# ThrowBot_TX_Main_Board.net
KiCad netlist of a schematic drawn in Altium Designer
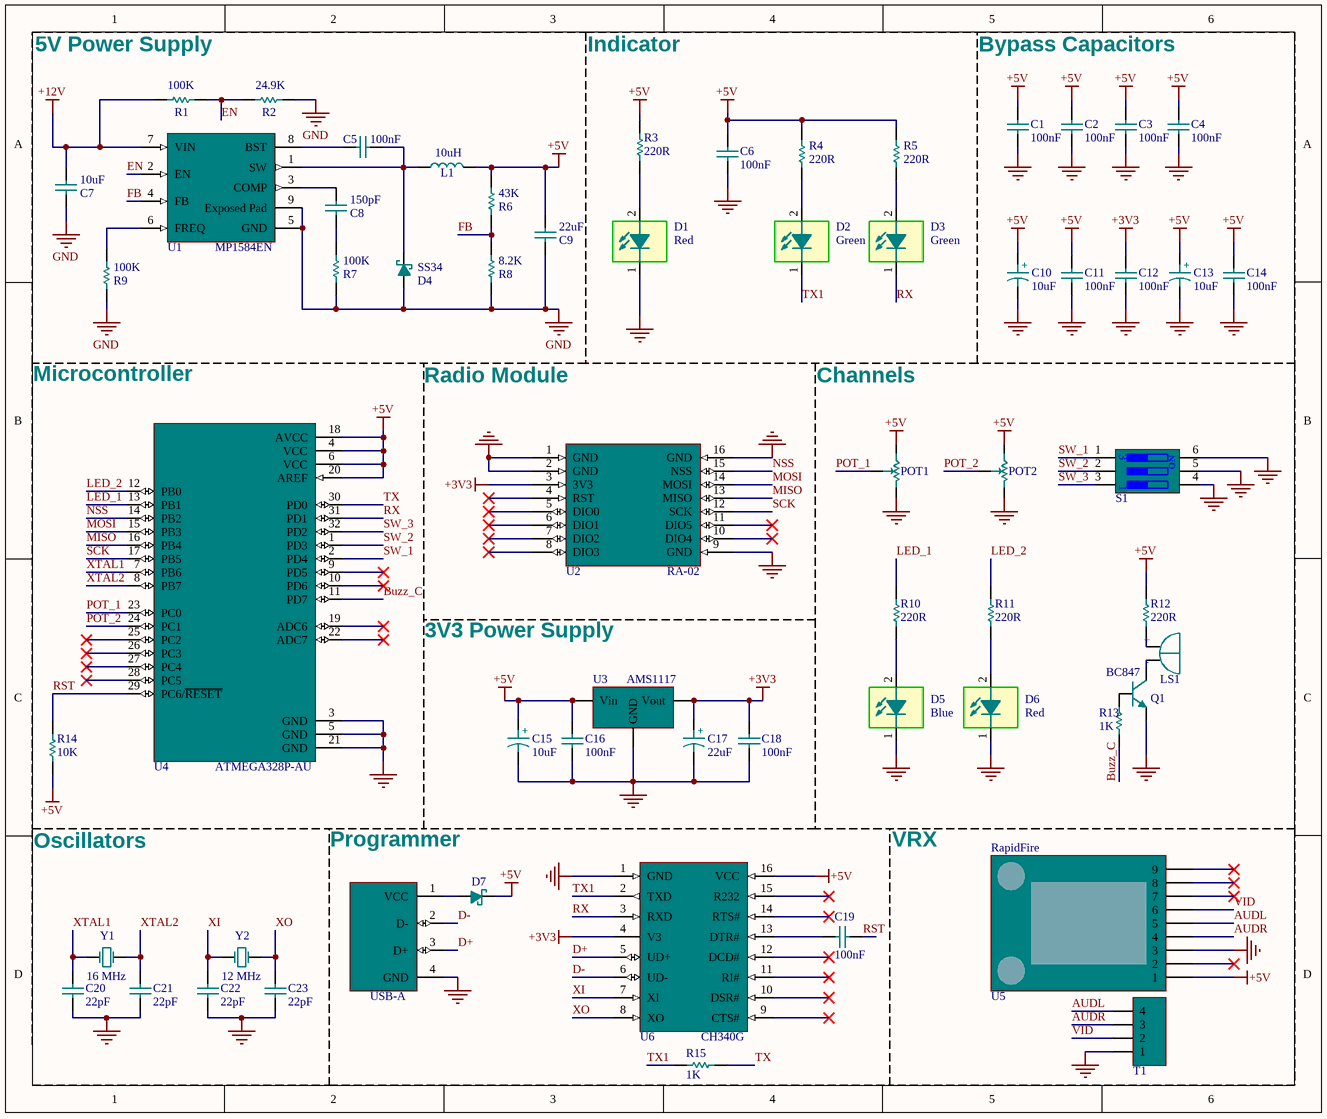
[diagram p0: ThrowBot_TX_Main_Board.SchDoc]

(export (version "E")
  (design (tool "Eeschema 10.0.6"))
  (components
    (comp (ref "C1")
      (value "Cap")
      (footprint "CAP 1206")
      (description "AVCC Cap")
      (fields (field (name "VAL-1") "100nF"))
      (libsource (lib "Throwbot") (part "Cap"))
    )
    (comp (ref "C2")
      (value "Cap")
      (footprint "CAP 1206")
      (description "VCC Cap")
      (fields (field (name "VAL-1") "100nF"))
      (libsource (lib "Throwbot") (part "Cap"))
    )
    (comp (ref "C3")
      (value "Cap")
      (footprint "CAP 1206")
      (description "VCC Cap")
      (fields (field (name "VAL-1") "100nF"))
      (libsource (lib "Throwbot") (part "Cap"))
    )
    (comp (ref "C4")
      (value "Cap")
      (footprint "CAP 1206")
      (description "AREF Cap")
      (fields (field (name "VAL-1") "100nF"))
      (libsource (lib "Throwbot") (part "Cap"))
    )
    (comp (ref "C5")
      (value "Cap")
      (footprint "CAP 1206")
      (description "1206 Capacitor")
      (fields (field (name "VAL-1") "100nF"))
      (libsource (lib "Throwbot") (part "Cap"))
    )
    (comp (ref "C6")
      (value "Cap")
      (footprint "CAP 1206")
      (description "USB to TTL Cap")
      (fields (field (name "VAL-1") "100nF"))
      (libsource (lib "Throwbot") (part "Cap"))
    )
    (comp (ref "C7")
      (value "Cap")
      (footprint "CAP 1206")
      (description "1206 Capacitor")
      (fields (field (name "VAL-4") "10uF"))
      (libsource (lib "Throwbot") (part "Cap"))
    )
    (comp (ref "C8")
      (value "Cap")
      (footprint "CAP 1206")
      (description "1206 Capacitor")
      (fields (field (name "VAL-5") "150pF"))
      (libsource (lib "Throwbot") (part "Cap"))
    )
    (comp (ref "C9")
      (value "Cap")
      (footprint "CAP 1206")
      (description "1206 Capacitor")
      (fields (field (name "VAL-3") "22uF"))
      (libsource (lib "Throwbot") (part "Cap"))
    )
    (comp (ref "C10")
      (value "Cap BiPolar")
      (footprint "CAP Tantalum Size B")
      (description "USB to TTL Cap")
      (fields (field (name "VAL-1") "10uF"))
      (libsource (lib "Throwbot") (part "Cap BiPolar"))
    )
    (comp (ref "C11")
      (value "Cap")
      (footprint "CAP 1206")
      (description "USB to TTL Cap")
      (fields (field (name "VAL-1") "100nF"))
      (libsource (lib "Throwbot") (part "Cap"))
    )
    (comp (ref "C12")
      (value "Cap")
      (footprint "CAP 1206")
      (description "USB to TTL Cap")
      (fields (field (name "VAL-1") "100nF"))
      (libsource (lib "Throwbot") (part "Cap"))
    )
    (comp (ref "C13")
      (value "Cap BiPolar")
      (footprint "CAP Tantalum Size B")
      (description "RapidFire Cap")
      (fields (field (name "VAL-1") "10uF"))
      (libsource (lib "Throwbot") (part "Cap BiPolar"))
    )
    (comp (ref "C14")
      (value "Cap")
      (footprint "CAP 1206")
      (description "RapidFire Cap")
      (fields (field (name "VAL-1") "100nF"))
      (libsource (lib "Throwbot") (part "Cap"))
    )
    (comp (ref "C15")
      (value "Cap BiPolar")
      (footprint "CAP Tantalum Size B")
      (description "3.3V Regulator Cap")
      (fields (field (name "VAL-1") "10uF"))
      (libsource (lib "Throwbot") (part "Cap BiPolar"))
    )
    (comp (ref "C16")
      (value "Cap")
      (footprint "CAP 1206")
      (description "3.3V Regulator Cap")
      (fields (field (name "VAL-1") "100nF"))
      (libsource (lib "Throwbot") (part "Cap"))
    )
    (comp (ref "C17")
      (value "Cap BiPolar")
      (footprint "CAP Tantalum Size B")
      (description "3.3V Regulator Cap")
      (fields (field (name "VAL-1") "22uF"))
      (libsource (lib "Throwbot") (part "Cap BiPolar"))
    )
    (comp (ref "C18")
      (value "Cap")
      (footprint "CAP 1206")
      (description "3.3V Regulator Cap")
      (fields (field (name "VAL-1") "100nF"))
      (libsource (lib "Throwbot") (part "Cap"))
    )
    (comp (ref "C19")
      (value "Cap")
      (footprint "CAP 1206")
      (description "Programmer Cap")
      (fields (field (name "VAL-1") "100nF"))
      (libsource (lib "Throwbot") (part "Cap"))
    )
    (comp (ref "C20")
      (value "Cap")
      (footprint "CAP 1206")
      (description "1206 Capacitor")
      (fields (field (name "VAL-2") "22pF"))
      (libsource (lib "Throwbot") (part "Cap"))
    )
    (comp (ref "C21")
      (value "Cap")
      (footprint "CAP 1206")
      (description "1206 Capacitor")
      (fields (field (name "VAL-2") "22pF"))
      (libsource (lib "Throwbot") (part "Cap"))
    )
    (comp (ref "C22")
      (value "Cap")
      (footprint "CAP 1206")
      (description "1206 Capacitor")
      (fields (field (name "VAL-2") "22pF"))
      (libsource (lib "Throwbot") (part "Cap"))
    )
    (comp (ref "C23")
      (value "Cap")
      (footprint "CAP 1206")
      (description "1206 Capacitor")
      (fields (field (name "VAL-2") "22pF"))
      (libsource (lib "Throwbot") (part "Cap"))
    )
    (comp (ref "D1")
      (value "LED")
      (footprint "LED 1206")
      (fields (field (name "COLOR-2") "Red"))
      (libsource (lib "Throwbot") (part "LED"))
    )
    (comp (ref "D2")
      (value "LED")
      (footprint "LED 1206")
      (fields (field (name "COLOR-3") "Green"))
      (libsource (lib "Throwbot") (part "LED"))
    )
    (comp (ref "D3")
      (value "LED")
      (footprint "LED 1206")
      (fields (field (name "COLOR-3") "Green"))
      (libsource (lib "Throwbot") (part "LED"))
    )
    (comp (ref "D4")
      (value "SS34")
      (footprint "SS34")
      (description "Diode Schottky 40 V 3A Surface Mount SMA")
      (fields (field (name "MF") "MDD"))
      (libsource (lib "Throwbot") (part "SS34"))
    )
    (comp (ref "D5")
      (value "LED")
      (footprint "LED 1206")
      (fields (field (name "COLOR-1") "Blue"))
      (libsource (lib "Throwbot") (part "LED"))
    )
    (comp (ref "D6")
      (value "LED")
      (footprint "LED 1206")
      (fields (field (name "COLOR-2") "Red"))
      (libsource (lib "Throwbot") (part "LED"))
    )
    (comp (ref "D7")
      (value "SS34")
      (footprint "SS34")
      (description "Diode Schottky 40 V 3A Surface Mount SMA")
      (libsource (lib "Throwbot") (part "SS34"))
    )
    (comp (ref "L1")
      (value "10uH")
      (footprint "IND 10uH")
      (description "Inductor")
      (fields (field (name "PUBLISHER") "Altium Limited"))
      (libsource (lib "Throwbot") (part "Inductor"))
    )
    (comp (ref "LS1")
      (value "Buzzer-5V")
      (footprint "Buzzer-5V")
      (libsource (lib "Throwbot") (part "Buzzer-5V"))
    )
    (comp (ref "POT1") (value "Pot") (footprint "Pot") (libsource (lib "Throwbot") (part "Pot")))
    (comp (ref "POT2") (value "Pot") (footprint "Pot") (libsource (lib "Throwbot") (part "Pot")))
    (comp (ref "Q1")
      (value "BC847")
      (footprint "BC847-SOT23")
      (description "NPN General-purpose Transistor")
      (fields (field (name "DESIGNER") "Abbas Basereh"))
      (libsource (lib "Throwbot") (part "BC847"))
    )
    (comp (ref "R1")
      (value "Resistor")
      (footprint "RES 1206")
      (fields (field (name "VAL-4") "100K"))
      (libsource (lib "Throwbot") (part "Resistor"))
    )
    (comp (ref "R2")
      (value "Resistor")
      (footprint "RES 1206")
      (fields (field (name "VAL-5") "24.9K"))
      (libsource (lib "Throwbot") (part "Resistor"))
    )
    (comp (ref "R3")
      (value "Resistor")
      (footprint "RES 1206")
      (fields (field (name "VAL-3") "220R"))
      (libsource (lib "Throwbot") (part "Resistor"))
    )
    (comp (ref "R4")
      (value "Resistor")
      (footprint "RES 1206")
      (fields (field (name "VAL-3") "220R"))
      (libsource (lib "Throwbot") (part "Resistor"))
    )
    (comp (ref "R5")
      (value "Resistor")
      (footprint "RES 1206")
      (fields (field (name "VAL-3") "220R"))
      (libsource (lib "Throwbot") (part "Resistor"))
    )
    (comp (ref "R6")
      (value "Resistor")
      (footprint "RES 1206")
      (fields (field (name "VAL-7") "43K"))
      (libsource (lib "Throwbot") (part "Resistor"))
    )
    (comp (ref "R7")
      (value "Resistor")
      (footprint "RES 1206")
      (fields (field (name "VAL-4") "100K"))
      (libsource (lib "Throwbot") (part "Resistor"))
    )
    (comp (ref "R8")
      (value "Resistor")
      (footprint "RES 1206")
      (fields (field (name "VAL-6") "8.2K"))
      (libsource (lib "Throwbot") (part "Resistor"))
    )
    (comp (ref "R9")
      (value "Resistor")
      (footprint "RES 1206")
      (fields (field (name "VAL-4") "100K"))
      (libsource (lib "Throwbot") (part "Resistor"))
    )
    (comp (ref "R10")
      (value "Resistor")
      (footprint "RES 1206")
      (fields (field (name "VAL-3") "220R"))
      (libsource (lib "Throwbot") (part "Resistor"))
    )
    (comp (ref "R11")
      (value "Resistor")
      (footprint "RES 1206")
      (fields (field (name "VAL-3") "220R"))
      (libsource (lib "Throwbot") (part "Resistor"))
    )
    (comp (ref "R12")
      (value "Resistor")
      (footprint "RES 1206")
      (fields (field (name "VAL-3") "220R"))
      (libsource (lib "Throwbot") (part "Resistor"))
    )
    (comp (ref "R13")
      (value "Resistor")
      (footprint "RES 1206")
      (fields (field (name "VAL-1") "1K"))
      (libsource (lib "Throwbot") (part "Resistor"))
    )
    (comp (ref "R14")
      (value "Resistor")
      (footprint "RES 1206")
      (fields (field (name "VAL-2") "10K"))
      (libsource (lib "Throwbot") (part "Resistor"))
    )
    (comp (ref "R15")
      (value "Resistor")
      (footprint "RES 1206")
      (fields (field (name "VAL-1") "1K"))
      (libsource (lib "Throwbot") (part "Resistor"))
    )
    (comp (ref "S1")
      (value "DIP Switch x3")
      (footprint "DIP Switch x3")
      (libsource (lib "Throwbot") (part "DIP Switch x3"))
    )
    (comp (ref "T1")
      (value "4 Pin Socket")
      (footprint "XH-4AW")
      (libsource (lib "Throwbot") (part "4 Pin Socket"))
    )
    (comp (ref "U1")
      (value "MP1584EN")
      (footprint "MP1584EN")
      (fields (field (name "MF") "Monolithic Power"))
      (libsource (lib "Throwbot") (part "MP1584EN"))
    )
    (comp (ref "U2")
      (value "RA-02")
      (footprint "RA-02")
      (description "LoRa RA-02")
      (libsource (lib "Throwbot") (part "RA-02"))
    )
    (comp (ref "U3")
      (value "AMS1117")
      (footprint "AMS1117")
      (description "3V3 Regulator")
      (libsource (lib "Throwbot") (part "AMS1117"))
    )
    (comp (ref "U4")
      (value "ATMEGA328P-AU")
      (footprint "ATmega328")
      (description "ATmega 328 Microcontroller")
      (libsource (lib "Throwbot") (part "ATMEGA328P-AU"))
    )
    (comp (ref "U5")
      (value "RapidFire")
      (footprint "RapidFire")
      (libsource (lib "Throwbot") (part "RapidFire"))
    )
    (comp (ref "U6") (value "CH340G") (footprint "CH340G") (libsource (lib "Throwbot") (part "CH340G")))
    (comp (ref "USB1") (value "USB-A") (footprint "USB-A-SMD") (libsource (lib "Throwbot") (part "USB-A")))
    (comp (ref "Y1")
      (value "XTAL")
      (footprint "Crystal-5032")
      (description "XTAL Crystal")
      (fields (field (name "VAL-2") "16 MHz"))
      (libsource (lib "Throwbot") (part "XTAL"))
    )
    (comp (ref "Y2")
      (value "XTAL")
      (footprint "Crystal-5032")
      (description "XTAL Crystal")
      (fields (field (name "VAL-1") "12 MHz"))
      (libsource (lib "Throwbot") (part "XTAL"))
    )
  )
  (nets
    (net (code "1") (name "+3V3") (class "Default")
      (node (ref "C12") (pin "1") (pinfunction "1_1") (pintype "passive"))
      (node (ref "C17") (pin "1") (pinfunction "1_1") (pintype "passive"))
      (node (ref "C18") (pin "1") (pinfunction "1_1") (pintype "passive"))
      (node (ref "U2") (pin "3") (pinfunction "3V3_3") (pintype "input"))
      (node (ref "U3") (pin "2") (pinfunction "Vout_2") (pintype "power_in"))
      (node (ref "U6") (pin "4") (pinfunction "V3_4") (pintype "passive"))
    )
    (net (code "2") (name "+5V") (class "Default")
      (node (ref "C1") (pin "1") (pinfunction "1_1") (pintype "passive"))
      (node (ref "C10") (pin "1") (pinfunction "1_1") (pintype "passive"))
      (node (ref "C11") (pin "1") (pinfunction "1_1") (pintype "passive"))
      (node (ref "C13") (pin "1") (pinfunction "1_1") (pintype "passive"))
      (node (ref "C14") (pin "1") (pinfunction "1_1") (pintype "passive"))
      (node (ref "C15") (pin "1") (pinfunction "1_1") (pintype "passive"))
      (node (ref "C16") (pin "1") (pinfunction "1_1") (pintype "passive"))
      (node (ref "C2") (pin "1") (pinfunction "1_1") (pintype "passive"))
      (node (ref "C3") (pin "1") (pinfunction "1_1") (pintype "passive"))
      (node (ref "C4") (pin "1") (pinfunction "1_1") (pintype "passive"))
      (node (ref "C6") (pin "1") (pinfunction "1_1") (pintype "passive"))
      (node (ref "C9") (pin "2") (pinfunction "2_2") (pintype "passive"))
      (node (ref "D7") (pin "2") (pinfunction "K_2") (pintype "passive"))
      (node (ref "L1") (pin "2") (pinfunction "2_2") (pintype "passive"))
      (node (ref "POT1") (pin "1") (pinfunction "CCW_1") (pintype "passive"))
      (node (ref "POT2") (pin "1") (pinfunction "CCW_1") (pintype "passive"))
      (node (ref "R12") (pin "2") (pinfunction "2_2") (pintype "passive"))
      (node (ref "R14") (pin "2") (pinfunction "2_2") (pintype "passive"))
      (node (ref "R3") (pin "2") (pinfunction "2_2") (pintype "passive"))
      (node (ref "R4") (pin "1") (pinfunction "1_1") (pintype "passive"))
      (node (ref "R5") (pin "1") (pinfunction "1_1") (pintype "passive"))
      (node (ref "R6") (pin "2") (pinfunction "2_2") (pintype "passive"))
      (node (ref "U3") (pin "3") (pinfunction "Vin_3") (pintype "power_in"))
      (node (ref "U4") (pin "18") (pinfunction "AVCC_18") (pintype "power_in"))
      (node (ref "U4") (pin "20") (pinfunction "AREF_20") (pintype "input"))
      (node (ref "U4") (pin "4") (pinfunction "VCC_4") (pintype "power_in"))
      (node (ref "U4") (pin "6") (pinfunction "VCC_6") (pintype "power_in"))
      (node (ref "U5") (pin "1") (pinfunction "1_1") (pintype "passive"))
      (node (ref "U6") (pin "16") (pinfunction "VCC_16") (pintype "input"))
    )
    (net (code "3") (name "+12V") (class "Default")
      (node (ref "C7") (pin "2") (pinfunction "2_2") (pintype "passive"))
      (node (ref "R1") (pin "2") (pinfunction "2_2") (pintype "passive"))
      (node (ref "U1") (pin "7") (pinfunction "VIN_7") (pintype "input"))
    )
    (net (code "4") (name "/AUDL") (class "Default")
      (node (ref "T1") (pin "4") (pinfunction "4_4") (pintype "passive"))
      (node (ref "U5") (pin "5") (pinfunction "5_5") (pintype "passive"))
    )
    (net (code "5") (name "/AUDR") (class "Default")
      (node (ref "T1") (pin "3") (pinfunction "3_3") (pintype "passive"))
      (node (ref "U5") (pin "4") (pinfunction "4_4") (pintype "passive"))
    )
    (net (code "6") (name "/Buzz_C") (class "Default")
      (node (ref "R13") (pin "1") (pinfunction "1_1") (pintype "passive"))
      (node (ref "U4") (pin "11") (pinfunction "PD7_11") (pintype "bidirectional"))
    )
    (net (code "7") (name "/D+") (class "Default")
      (node (ref "U6") (pin "5") (pinfunction "UD+_5") (pintype "bidirectional"))
      (node (ref "USB1") (pin "3") (pinfunction "D+_3") (pintype "bidirectional"))
    )
    (net (code "8") (name "/D-") (class "Default")
      (node (ref "U6") (pin "6") (pinfunction "UD-_6") (pintype "bidirectional"))
      (node (ref "USB1") (pin "2") (pinfunction "D-_2") (pintype "bidirectional"))
    )
    (net (code "9") (name "/EN") (class "Default")
      (node (ref "R1") (pin "1") (pinfunction "1_1") (pintype "passive"))
      (node (ref "R2") (pin "1") (pinfunction "1_1") (pintype "passive"))
      (node (ref "U1") (pin "2") (pinfunction "EN_2") (pintype "input"))
    )
    (net (code "10") (name "/FB") (class "Default")
      (node (ref "R6") (pin "1") (pinfunction "1_1") (pintype "passive"))
      (node (ref "R8") (pin "2") (pinfunction "2_2") (pintype "passive"))
      (node (ref "U1") (pin "4") (pinfunction "FB_4") (pintype "input"))
    )
    (net (code "11") (name "/LED_1") (class "Default")
      (node (ref "R10") (pin "2") (pinfunction "2_2") (pintype "passive"))
      (node (ref "U4") (pin "13") (pinfunction "PB1_13") (pintype "bidirectional"))
    )
    (net (code "12") (name "/LED_2") (class "Default")
      (node (ref "R11") (pin "2") (pinfunction "2_2") (pintype "passive"))
      (node (ref "U4") (pin "12") (pinfunction "PB0_12") (pintype "bidirectional"))
    )
    (net (code "13") (name "/MISO") (class "Default")
      (node (ref "U2") (pin "13") (pinfunction "MISO_13") (pintype "bidirectional"))
      (node (ref "U4") (pin "16") (pinfunction "PB4_16") (pintype "bidirectional"))
    )
    (net (code "14") (name "/MOSI") (class "Default")
      (node (ref "U2") (pin "14") (pinfunction "MOSI_14") (pintype "bidirectional"))
      (node (ref "U4") (pin "15") (pinfunction "PB3_15") (pintype "bidirectional"))
    )
    (net (code "15") (name "/NSS") (class "Default")
      (node (ref "U2") (pin "15") (pinfunction "NSS_15") (pintype "bidirectional"))
      (node (ref "U4") (pin "14") (pinfunction "PB2_14") (pintype "bidirectional"))
    )
    (net (code "16") (name "/POT_1") (class "Default")
      (node (ref "POT1") (pin "3") (pinfunction "SetPoint_3") (pintype "passive"))
      (node (ref "U4") (pin "23") (pinfunction "PC0_23") (pintype "bidirectional"))
    )
    (net (code "17") (name "/POT_2") (class "Default")
      (node (ref "POT2") (pin "3") (pinfunction "SetPoint_3") (pintype "passive"))
      (node (ref "U4") (pin "24") (pinfunction "PC1_24") (pintype "bidirectional"))
    )
    (net (code "18") (name "/RST") (class "Default")
      (node (ref "C19") (pin "1") (pinfunction "1_1") (pintype "passive"))
      (node (ref "R14") (pin "1") (pinfunction "1_1") (pintype "passive"))
      (node (ref "U4") (pin "29") (pinfunction "PC6/~{RESET}_29") (pintype "bidirectional"))
    )
    (net (code "19") (name "/RX") (class "Default")
      (node (ref "D3") (pin "1") (pinfunction "1_1") (pintype "passive"))
      (node (ref "U4") (pin "31") (pinfunction "PD1_31") (pintype "bidirectional"))
      (node (ref "U6") (pin "3") (pinfunction "RXD_3") (pintype "input"))
    )
    (net (code "20") (name "/SCK") (class "Default")
      (node (ref "U2") (pin "12") (pinfunction "SCK_12") (pintype "bidirectional"))
      (node (ref "U4") (pin "17") (pinfunction "PB5_17") (pintype "bidirectional"))
    )
    (net (code "21") (name "/SW_1") (class "Default")
      (node (ref "S1") (pin "1") (pinfunction "1_1") (pintype "passive"))
      (node (ref "U4") (pin "2") (pinfunction "PD4_2") (pintype "bidirectional"))
    )
    (net (code "22") (name "/SW_2") (class "Default")
      (node (ref "S1") (pin "2") (pinfunction "2_2") (pintype "passive"))
      (node (ref "U4") (pin "1") (pinfunction "PD3_1") (pintype "bidirectional"))
    )
    (net (code "23") (name "/SW_3") (class "Default")
      (node (ref "S1") (pin "3") (pinfunction "3_3") (pintype "passive"))
      (node (ref "U4") (pin "32") (pinfunction "PD2_32") (pintype "bidirectional"))
    )
    (net (code "24") (name "/TX") (class "Default")
      (node (ref "R15") (pin "2") (pinfunction "2_2") (pintype "passive"))
      (node (ref "U4") (pin "30") (pinfunction "PD0_30") (pintype "bidirectional"))
    )
    (net (code "25") (name "/TX1") (class "Default")
      (node (ref "D2") (pin "1") (pinfunction "1_1") (pintype "passive"))
      (node (ref "R15") (pin "1") (pinfunction "1_1") (pintype "passive"))
      (node (ref "U6") (pin "2") (pinfunction "TXD_2") (pintype "output"))
    )
    (net (code "26") (name "/VID") (class "Default")
      (node (ref "T1") (pin "2") (pinfunction "2_2") (pintype "passive"))
      (node (ref "U5") (pin "6") (pinfunction "6_6") (pintype "passive"))
    )
    (net (code "27") (name "/XI") (class "Default")
      (node (ref "C22") (pin "2") (pinfunction "2_2") (pintype "passive"))
      (node (ref "U6") (pin "7") (pinfunction "XI_7") (pintype "input"))
      (node (ref "Y2") (pin "1") (pinfunction "OSC1_1") (pintype "passive"))
    )
    (net (code "28") (name "/XO") (class "Default")
      (node (ref "C23") (pin "2") (pinfunction "2_2") (pintype "passive"))
      (node (ref "U6") (pin "8") (pinfunction "XO_8") (pintype "input"))
      (node (ref "Y2") (pin "2") (pinfunction "OSC2_2") (pintype "passive"))
    )
    (net (code "29") (name "/XTAL1") (class "Default")
      (node (ref "C20") (pin "2") (pinfunction "2_2") (pintype "passive"))
      (node (ref "U4") (pin "7") (pinfunction "PB6_7") (pintype "bidirectional"))
      (node (ref "Y1") (pin "1") (pinfunction "OSC1_1") (pintype "passive"))
    )
    (net (code "30") (name "/XTAL2") (class "Default")
      (node (ref "C21") (pin "2") (pinfunction "2_2") (pintype "passive"))
      (node (ref "U4") (pin "8") (pinfunction "PB7_8") (pintype "bidirectional"))
      (node (ref "Y1") (pin "2") (pinfunction "OSC2_2") (pintype "passive"))
    )
    (net (code "31") (name "GND") (class "Default")
      (node (ref "C1") (pin "2") (pinfunction "2_2") (pintype "passive"))
      (node (ref "C10") (pin "2") (pinfunction "2_2") (pintype "passive"))
      (node (ref "C11") (pin "2") (pinfunction "2_2") (pintype "passive"))
      (node (ref "C12") (pin "2") (pinfunction "2_2") (pintype "passive"))
      (node (ref "C13") (pin "2") (pinfunction "2_2") (pintype "passive"))
      (node (ref "C14") (pin "2") (pinfunction "2_2") (pintype "passive"))
      (node (ref "C15") (pin "2") (pinfunction "2_2") (pintype "passive"))
      (node (ref "C16") (pin "2") (pinfunction "2_2") (pintype "passive"))
      (node (ref "C17") (pin "2") (pinfunction "2_2") (pintype "passive"))
      (node (ref "C18") (pin "2") (pinfunction "2_2") (pintype "passive"))
      (node (ref "C2") (pin "2") (pinfunction "2_2") (pintype "passive"))
      (node (ref "C20") (pin "1") (pinfunction "1_1") (pintype "passive"))
      (node (ref "C21") (pin "1") (pinfunction "1_1") (pintype "passive"))
      (node (ref "C22") (pin "1") (pinfunction "1_1") (pintype "passive"))
      (node (ref "C23") (pin "1") (pinfunction "1_1") (pintype "passive"))
      (node (ref "C3") (pin "2") (pinfunction "2_2") (pintype "passive"))
      (node (ref "C4") (pin "2") (pinfunction "2_2") (pintype "passive"))
      (node (ref "C6") (pin "2") (pinfunction "2_2") (pintype "passive"))
      (node (ref "C7") (pin "1") (pinfunction "1_1") (pintype "passive"))
      (node (ref "C9") (pin "1") (pinfunction "1_1") (pintype "passive"))
      (node (ref "D1") (pin "1") (pinfunction "1_1") (pintype "passive"))
      (node (ref "D4") (pin "1") (pinfunction "A_1") (pintype "passive"))
      (node (ref "D5") (pin "1") (pinfunction "1_1") (pintype "passive"))
      (node (ref "D6") (pin "1") (pinfunction "1_1") (pintype "passive"))
      (node (ref "POT1") (pin "2") (pinfunction "CW_2") (pintype "passive"))
      (node (ref "POT2") (pin "2") (pinfunction "CW_2") (pintype "passive"))
      (node (ref "Q1") (pin "2") (pinfunction "E_2") (pintype "passive"))
      (node (ref "R2") (pin "2") (pinfunction "2_2") (pintype "passive"))
      (node (ref "R7") (pin "1") (pinfunction "1_1") (pintype "passive"))
      (node (ref "R8") (pin "1") (pinfunction "1_1") (pintype "passive"))
      (node (ref "R9") (pin "1") (pinfunction "1_1") (pintype "passive"))
      (node (ref "S1") (pin "4") (pinfunction "4_4") (pintype "passive"))
      (node (ref "S1") (pin "5") (pinfunction "5_5") (pintype "passive"))
      (node (ref "S1") (pin "6") (pinfunction "6_6") (pintype "passive"))
      (node (ref "T1") (pin "1") (pinfunction "1_1") (pintype "passive"))
      (node (ref "U1") (pin "5") (pinfunction "GND_5") (pintype "power_in"))
      (node (ref "U1") (pin "9") (pinfunction "Exposed_Pad_9") (pintype "power_in"))
      (node (ref "U2") (pin "1") (pinfunction "GND_1") (pintype "input"))
      (node (ref "U2") (pin "16") (pinfunction "GND_16") (pintype "input"))
      (node (ref "U2") (pin "2") (pinfunction "GND_2") (pintype "input"))
      (node (ref "U2") (pin "9") (pinfunction "GND_9") (pintype "input"))
      (node (ref "U3") (pin "1") (pinfunction "GND_1") (pintype "power_in"))
      (node (ref "U4") (pin "21") (pinfunction "GND_21") (pintype "power_in"))
      (node (ref "U4") (pin "3") (pinfunction "GND_3") (pintype "power_in"))
      (node (ref "U4") (pin "5") (pinfunction "GND_5") (pintype "power_in"))
      (node (ref "U5") (pin "3") (pinfunction "3_3") (pintype "passive"))
      (node (ref "U6") (pin "1") (pinfunction "GND_1") (pintype "input"))
      (node (ref "USB1") (pin "4") (pinfunction "GND_4") (pintype "power_in"))
    )
    (net (code "32") (name "Net-(C8-Pad1)") (class "Default")
      (node (ref "C8") (pin "1") (pinfunction "1_1") (pintype "passive"))
      (node (ref "R7") (pin "2") (pinfunction "2_2") (pintype "passive"))
    )
    (net (code "33") (name "Net-(D1-Pad2)") (class "Default")
      (node (ref "D1") (pin "2") (pinfunction "2_2") (pintype "passive"))
      (node (ref "R3") (pin "1") (pinfunction "1_1") (pintype "passive"))
    )
    (net (code "34") (name "Net-(D2-Pad2)") (class "Default")
      (node (ref "D2") (pin "2") (pinfunction "2_2") (pintype "passive"))
      (node (ref "R4") (pin "2") (pinfunction "2_2") (pintype "passive"))
    )
    (net (code "35") (name "Net-(D3-Pad2)") (class "Default")
      (node (ref "D3") (pin "2") (pinfunction "2_2") (pintype "passive"))
      (node (ref "R5") (pin "2") (pinfunction "2_2") (pintype "passive"))
    )
    (net (code "36") (name "Net-(D4-K)") (class "Default")
      (node (ref "C5") (pin "1") (pinfunction "1_1") (pintype "passive"))
      (node (ref "D4") (pin "2") (pinfunction "K_2") (pintype "passive"))
      (node (ref "L1") (pin "1") (pinfunction "1_1") (pintype "passive"))
      (node (ref "U1") (pin "1") (pinfunction "SW_1") (pintype "output"))
    )
    (net (code "37") (name "Net-(D5-Pad2)") (class "Default")
      (node (ref "D5") (pin "2") (pinfunction "2_2") (pintype "passive"))
      (node (ref "R10") (pin "1") (pinfunction "1_1") (pintype "passive"))
    )
    (net (code "38") (name "Net-(D6-Pad2)") (class "Default")
      (node (ref "D6") (pin "2") (pinfunction "2_2") (pintype "passive"))
      (node (ref "R11") (pin "1") (pinfunction "1_1") (pintype "passive"))
    )
    (net (code "39") (name "Net-(D7-A)") (class "Default")
      (node (ref "D7") (pin "1") (pinfunction "A_1") (pintype "passive"))
      (node (ref "USB1") (pin "1") (pinfunction "VCC_1") (pintype "power_in"))
    )
    (net (code "40") (name "Net-(LS1-NEG)") (class "Default")
      (node (ref "LS1") (pin "N") (pinfunction "NEG_N") (pintype "passive"))
      (node (ref "Q1") (pin "3") (pinfunction "C_3") (pintype "passive"))
    )
    (net (code "41") (name "Net-(LS1-POS)") (class "Default")
      (node (ref "LS1") (pin "P") (pinfunction "POS_P") (pintype "passive"))
      (node (ref "R12") (pin "1") (pinfunction "1_1") (pintype "passive"))
    )
    (net (code "42") (name "Net-(Q1-B)") (class "Default")
      (node (ref "Q1") (pin "1") (pinfunction "B_1") (pintype "passive"))
      (node (ref "R13") (pin "2") (pinfunction "2_2") (pintype "passive"))
    )
    (net (code "43") (name "Net-(U1-BST)") (class "Default")
      (node (ref "C5") (pin "2") (pinfunction "2_2") (pintype "passive"))
      (node (ref "U1") (pin "8") (pinfunction "BST_8") (pintype "passive"))
    )
    (net (code "44") (name "Net-(U1-COMP)") (class "Default")
      (node (ref "C8") (pin "2") (pinfunction "2_2") (pintype "passive"))
      (node (ref "U1") (pin "3") (pinfunction "COMP_3") (pintype "output"))
    )
    (net (code "45") (name "Net-(U1-FREQ)") (class "Default")
      (node (ref "R9") (pin "2") (pinfunction "2_2") (pintype "passive"))
      (node (ref "U1") (pin "6") (pinfunction "FREQ_6") (pintype "input"))
    )
    (net (code "46") (name "Net-(U6-DTR#)") (class "Default")
      (node (ref "C19") (pin "2") (pinfunction "2_2") (pintype "passive"))
      (node (ref "U6") (pin "13") (pinfunction "DTR#_13") (pintype "input"))
    )
    (net (code "47") (name "unconnected-(U2-DIO0-Pad5)") (class "Default")
      (node (ref "U2") (pin "5") (pinfunction "DIO0_5") (pintype "bidirectional+no_connect"))
    )
    (net (code "48") (name "unconnected-(U2-DIO1-Pad6)") (class "Default")
      (node (ref "U2") (pin "6") (pinfunction "DIO1_6") (pintype "bidirectional+no_connect"))
    )
    (net (code "49") (name "unconnected-(U2-DIO2-Pad7)") (class "Default")
      (node (ref "U2") (pin "7") (pinfunction "DIO2_7") (pintype "bidirectional+no_connect"))
    )
    (net (code "50") (name "unconnected-(U2-DIO3-Pad8)") (class "Default")
      (node (ref "U2") (pin "8") (pinfunction "DIO3_8") (pintype "bidirectional+no_connect"))
    )
    (net (code "51") (name "unconnected-(U2-DIO4-Pad10)") (class "Default")
      (node (ref "U2") (pin "10") (pinfunction "DIO4_10") (pintype "bidirectional+no_connect"))
    )
    (net (code "52") (name "unconnected-(U2-DIO5-Pad11)") (class "Default")
      (node (ref "U2") (pin "11") (pinfunction "DIO5_11") (pintype "bidirectional+no_connect"))
    )
    (net (code "53") (name "unconnected-(U2-RST-Pad4)") (class "Default")
      (node (ref "U2") (pin "4") (pinfunction "RST_4") (pintype "input+no_connect"))
    )
    (net (code "54") (name "unconnected-(U4-ADC6-Pad19)") (class "Default")
      (node (ref "U4") (pin "19") (pinfunction "ADC6_19") (pintype "bidirectional+no_connect"))
    )
    (net (code "55") (name "unconnected-(U4-ADC7-Pad22)") (class "Default")
      (node (ref "U4") (pin "22") (pinfunction "ADC7_22") (pintype "bidirectional+no_connect"))
    )
    (net (code "56") (name "unconnected-(U4-PC2-Pad25)") (class "Default")
      (node (ref "U4") (pin "25") (pinfunction "PC2_25") (pintype "bidirectional+no_connect"))
    )
    (net (code "57") (name "unconnected-(U4-PC3-Pad26)") (class "Default")
      (node (ref "U4") (pin "26") (pinfunction "PC3_26") (pintype "bidirectional+no_connect"))
    )
    (net (code "58") (name "unconnected-(U4-PC4-Pad27)") (class "Default")
      (node (ref "U4") (pin "27") (pinfunction "PC4_27") (pintype "bidirectional+no_connect"))
    )
    (net (code "59") (name "unconnected-(U4-PC5-Pad28)") (class "Default")
      (node (ref "U4") (pin "28") (pinfunction "PC5_28") (pintype "bidirectional+no_connect"))
    )
    (net (code "60") (name "unconnected-(U4-PD5-Pad9)") (class "Default")
      (node (ref "U4") (pin "9") (pinfunction "PD5_9") (pintype "bidirectional+no_connect"))
    )
    (net (code "61") (name "unconnected-(U4-PD6-Pad10)") (class "Default")
      (node (ref "U4") (pin "10") (pinfunction "PD6_10") (pintype "bidirectional+no_connect"))
    )
    (net (code "62") (name "unconnected-(U5-Pad2)") (class "Default")
      (node (ref "U5") (pin "2") (pinfunction "2_2") (pintype "passive+no_connect"))
    )
    (net (code "63") (name "unconnected-(U5-Pad7)") (class "Default")
      (node (ref "U5") (pin "7") (pinfunction "7_7") (pintype "passive+no_connect"))
    )
    (net (code "64") (name "unconnected-(U5-Pad8)") (class "Default")
      (node (ref "U5") (pin "8") (pinfunction "8_8") (pintype "passive+no_connect"))
    )
    (net (code "65") (name "unconnected-(U5-Pad9)") (class "Default")
      (node (ref "U5") (pin "9") (pinfunction "9_9") (pintype "passive+no_connect"))
    )
    (net (code "66") (name "unconnected-(U6-CTS#-Pad9)") (class "Default")
      (node (ref "U6") (pin "9") (pinfunction "CTS#_9") (pintype "input+no_connect"))
    )
    (net (code "67") (name "unconnected-(U6-DCD#-Pad12)") (class "Default")
      (node (ref "U6") (pin "12") (pinfunction "DCD#_12") (pintype "input+no_connect"))
    )
    (net (code "68") (name "unconnected-(U6-DSR#-Pad10)") (class "Default")
      (node (ref "U6") (pin "10") (pinfunction "DSR#_10") (pintype "input+no_connect"))
    )
    (net (code "69") (name "unconnected-(U6-R232-Pad15)") (class "Default")
      (node (ref "U6") (pin "15") (pinfunction "R232_15") (pintype "input+no_connect"))
    )
    (net (code "70") (name "unconnected-(U6-RI#-Pad11)") (class "Default")
      (node (ref "U6") (pin "11") (pinfunction "RI#_11") (pintype "input+no_connect"))
    )
    (net (code "71") (name "unconnected-(U6-RTS#-Pad14)") (class "Default")
      (node (ref "U6") (pin "14") (pinfunction "RTS#_14") (pintype "input+no_connect"))
    )
  )
)
